# ChassisCab-mega328.net
KiCad netlist of a schematic drawn in EAGLE
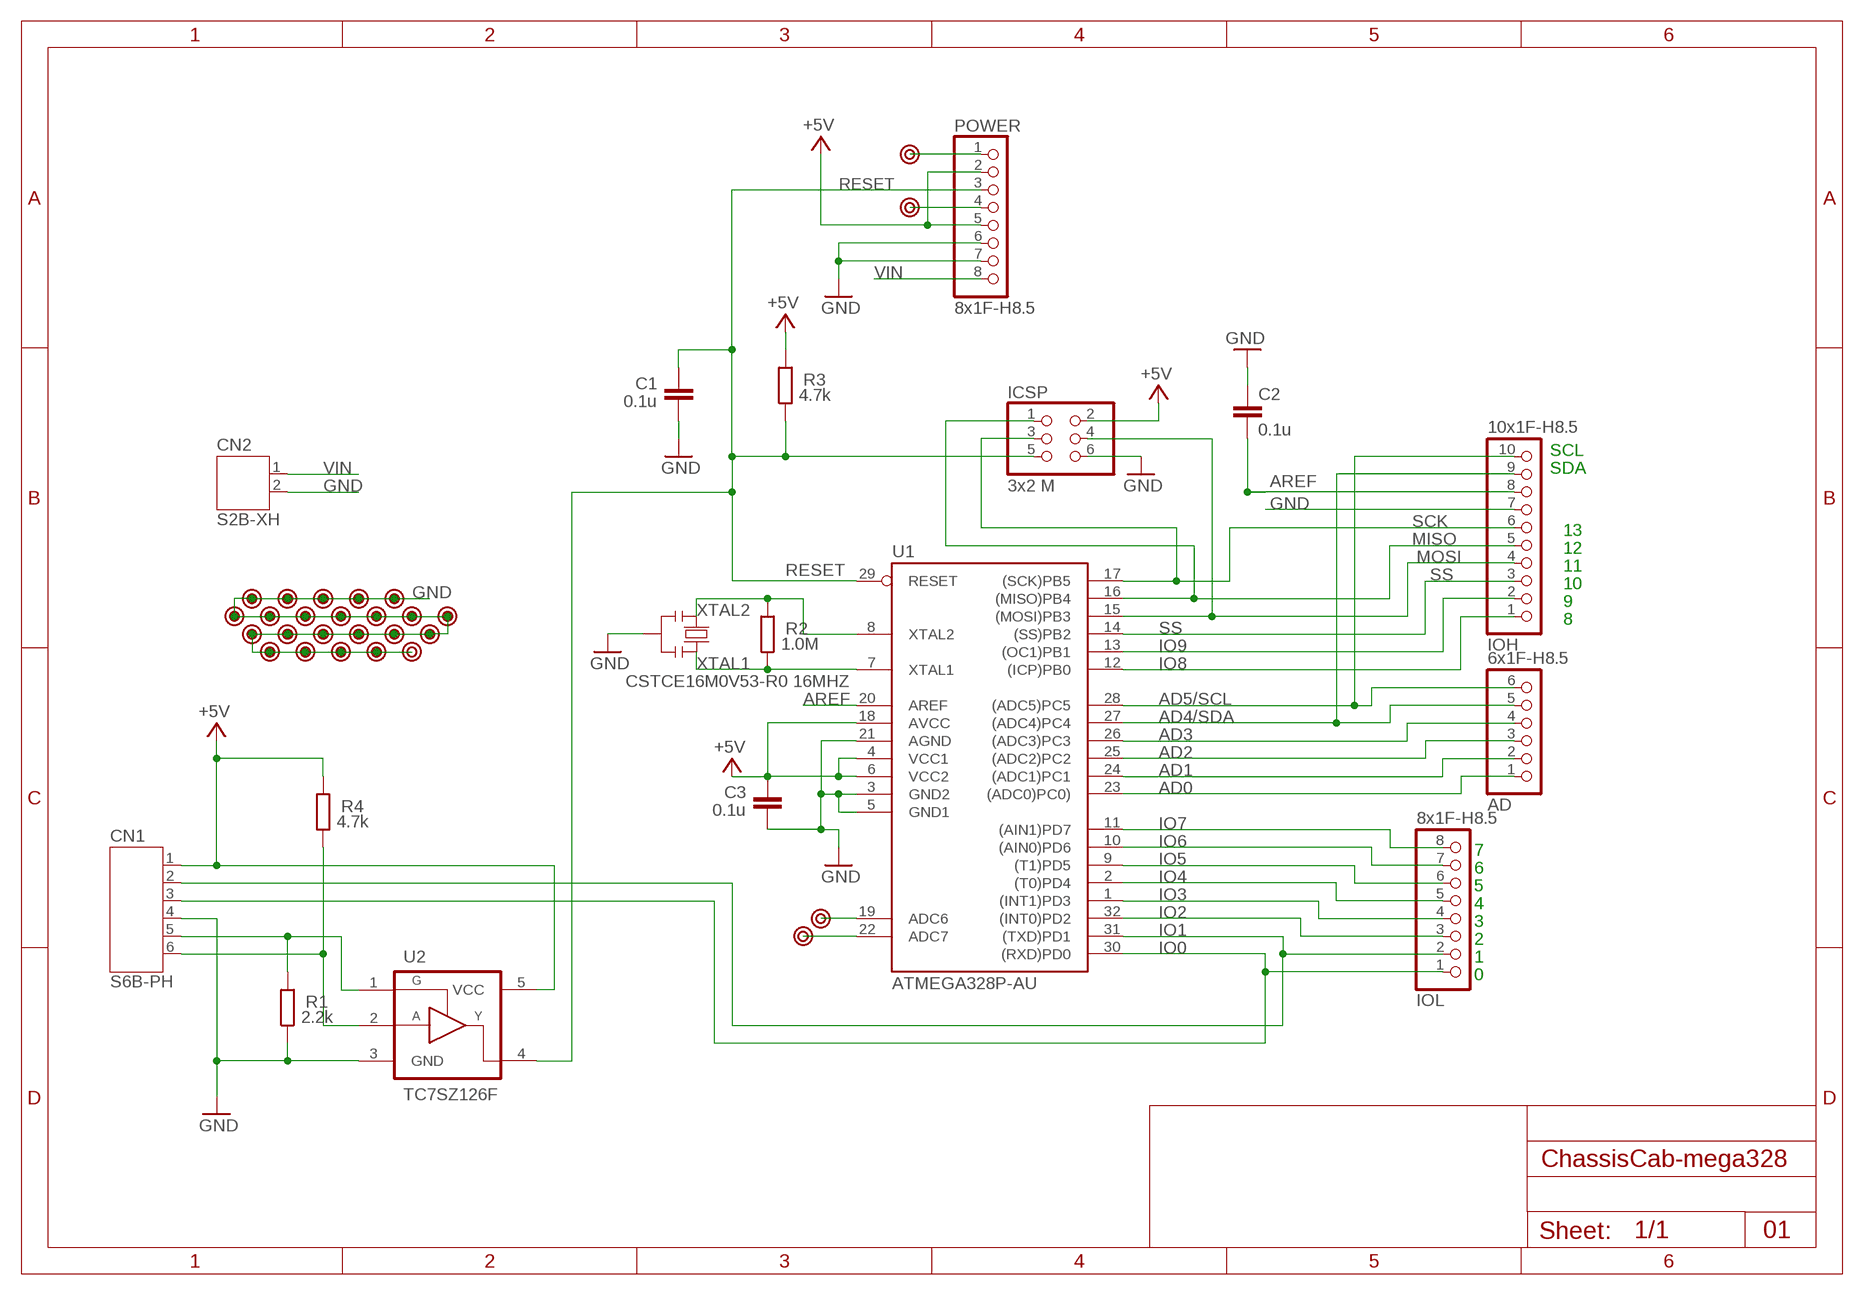
[diagram p0: schematic, sheet 1]

(export (version "E")
  (design (tool "Eeschema 10.0.6"))
  (components
    (comp (ref "AD")
      (value "6x1F-H8.5")
      (footprint "eagle-import:1X06")
      (libsource (lib "eagle-import") (part "PINHD-1X6"))
    )
    (comp (ref "C1")
      (value "0.1u")
      (footprint "eagle-import:C0603")
      (libsource (lib "eagle-import") (part "C-EUC0603"))
    )
    (comp (ref "C2")
      (value "0.1u")
      (footprint "eagle-import:C0603")
      (libsource (lib "eagle-import") (part "C-EUC0603"))
    )
    (comp (ref "C3")
      (value "0.1u")
      (footprint "eagle-import:C0603")
      (libsource (lib "eagle-import") (part "C-EUC0603"))
    )
    (comp (ref "CN1")
      (value "S6B-PH")
      (footprint "eagle-import:S6B-PH")
      (libsource (lib "eagle-import") (part "S6B-PH"))
    )
    (comp (ref "CN2")
      (value "S2B-XH")
      (footprint "eagle-import:S2B-XH")
      (libsource (lib "eagle-import") (part "S2B-XH"))
    )
    (comp (ref "ICSP")
      (value "3x2 M")
      (footprint "eagle-import:2X03")
      (libsource (lib "eagle-import") (part "PINHD-2X3"))
    )
    (comp (ref "IOH")
      (value "10x1F-H8.5")
      (footprint "eagle-import:1X10")
      (libsource (lib "eagle-import") (part "PINHD-1X10_ARD"))
    )
    (comp (ref "IOL")
      (value "8x1F-H8.5")
      (footprint "eagle-import:1X08")
      (libsource (lib "eagle-import") (part "PINHD-1X8"))
    )
    (comp (ref "POWER")
      (value "8x1F-H8.5")
      (footprint "eagle-import:1X08")
      (libsource (lib "eagle-import") (part "PINHD-1X8"))
    )
    (comp (ref "R1")
      (value "2.2k")
      (footprint "eagle-import:R0603")
      (libsource (lib "eagle-import") (part "R-EU_R0603"))
    )
    (comp (ref "R2")
      (value "1.0M")
      (footprint "eagle-import:R0603")
      (libsource (lib "eagle-import") (part "R-EU_R0603"))
    )
    (comp (ref "R3")
      (value "4.7k")
      (footprint "eagle-import:R0603")
      (libsource (lib "eagle-import") (part "R-EU_R0603"))
    )
    (comp (ref "R4")
      (value "4.7k")
      (footprint "eagle-import:R0603")
      (libsource (lib "eagle-import") (part "R-EU_R0603"))
    )
    (comp (ref "U$1")
      (value "PAD")
      (footprint "eagle-import:PAD")
      (libsource (lib "eagle-import") (part "PAD"))
    )
    (comp (ref "U$2")
      (value "PAD")
      (footprint "eagle-import:PAD")
      (libsource (lib "eagle-import") (part "PAD"))
    )
    (comp (ref "U$3")
      (value "PAD")
      (footprint "eagle-import:PAD")
      (libsource (lib "eagle-import") (part "PAD"))
    )
    (comp (ref "U$4")
      (value "PAD")
      (footprint "eagle-import:PAD")
      (libsource (lib "eagle-import") (part "PAD"))
    )
    (comp (ref "U$5")
      (value "PAD")
      (footprint "eagle-import:PAD")
      (libsource (lib "eagle-import") (part "PAD"))
    )
    (comp (ref "U$6")
      (value "PAD")
      (footprint "eagle-import:PAD")
      (libsource (lib "eagle-import") (part "PAD"))
    )
    (comp (ref "U$7")
      (value "PAD")
      (footprint "eagle-import:PAD")
      (libsource (lib "eagle-import") (part "PAD"))
    )
    (comp (ref "U$8")
      (value "PAD")
      (footprint "eagle-import:PAD")
      (libsource (lib "eagle-import") (part "PAD"))
    )
    (comp (ref "U$9")
      (value "PAD")
      (footprint "eagle-import:PAD")
      (libsource (lib "eagle-import") (part "PAD"))
    )
    (comp (ref "U$10")
      (value "PAD")
      (footprint "eagle-import:PAD")
      (libsource (lib "eagle-import") (part "PAD"))
    )
    (comp (ref "U$11")
      (value "PAD")
      (footprint "eagle-import:PAD")
      (libsource (lib "eagle-import") (part "PAD"))
    )
    (comp (ref "U$12")
      (value "PAD")
      (footprint "eagle-import:PAD")
      (libsource (lib "eagle-import") (part "PAD"))
    )
    (comp (ref "U$13")
      (value "PAD")
      (footprint "eagle-import:PAD")
      (libsource (lib "eagle-import") (part "PAD"))
    )
    (comp (ref "U$14")
      (value "PAD")
      (footprint "eagle-import:PAD")
      (libsource (lib "eagle-import") (part "PAD"))
    )
    (comp (ref "U$15")
      (value "PAD")
      (footprint "eagle-import:PAD")
      (libsource (lib "eagle-import") (part "PAD"))
    )
    (comp (ref "U$16")
      (value "PAD")
      (footprint "eagle-import:PAD")
      (libsource (lib "eagle-import") (part "PAD"))
    )
    (comp (ref "U$17")
      (value "PAD")
      (footprint "eagle-import:PAD")
      (libsource (lib "eagle-import") (part "PAD"))
    )
    (comp (ref "U$18")
      (value "PAD")
      (footprint "eagle-import:PAD")
      (libsource (lib "eagle-import") (part "PAD"))
    )
    (comp (ref "U$19")
      (value "PAD")
      (footprint "eagle-import:PAD")
      (libsource (lib "eagle-import") (part "PAD"))
    )
    (comp (ref "U$20")
      (value "PAD")
      (footprint "eagle-import:PAD")
      (libsource (lib "eagle-import") (part "PAD"))
    )
    (comp (ref "U$21")
      (value "PAD")
      (footprint "eagle-import:PAD")
      (libsource (lib "eagle-import") (part "PAD"))
    )
    (comp (ref "U$22")
      (value "PAD")
      (footprint "eagle-import:PAD")
      (libsource (lib "eagle-import") (part "PAD"))
    )
    (comp (ref "U$23")
      (value "PAD")
      (footprint "eagle-import:PAD")
      (libsource (lib "eagle-import") (part "PAD"))
    )
    (comp (ref "U$24")
      (value "PAD")
      (footprint "eagle-import:PAD")
      (libsource (lib "eagle-import") (part "PAD"))
    )
    (comp (ref "U$25")
      (value "PAD")
      (footprint "eagle-import:PAD")
      (libsource (lib "eagle-import") (part "PAD"))
    )
    (comp (ref "U$26")
      (value "PAD")
      (footprint "eagle-import:PAD")
      (libsource (lib "eagle-import") (part "PAD"))
    )
    (comp (ref "U$27")
      (value "PAD")
      (footprint "eagle-import:PAD")
      (libsource (lib "eagle-import") (part "PAD"))
    )
    (comp (ref "U1")
      (value "ATMEGA328P-AU")
      (footprint "eagle-import:TQFP32")
      (libsource (lib "eagle-import") (part "ATMEGA328P-AU"))
    )
    (comp (ref "U2")
      (value "TC7SZ126F")
      (footprint "eagle-import:SMV")
      (libsource (lib "eagle-import") (part "TC7SZ126F"))
    )
    (comp (ref "X1")
      (value "CSTCE16M0V53-R0 16MHZ")
      (footprint "eagle-import:CSTCE_V")
      (libsource (lib "eagle-import") (part "CSTCE16M0V53-R0"))
    )
  )
  (nets
    (net (code "1") (name "+5V") (class "Default")
      (node (ref "C3") (pin "2") (pinfunction "2_2") (pintype "passive"))
      (node (ref "CN1") (pin "1") (pinfunction "1_1") (pintype "passive"))
      (node (ref "ICSP") (pin "2") (pinfunction "2_2") (pintype "passive"))
      (node (ref "POWER") (pin "2") (pinfunction "2_2") (pintype "passive"))
      (node (ref "POWER") (pin "5") (pinfunction "5_5") (pintype "passive"))
      (node (ref "R3") (pin "2") (pinfunction "2_2") (pintype "passive"))
      (node (ref "R4") (pin "2") (pinfunction "2_2") (pintype "passive"))
      (node (ref "U1") (pin "18") (pinfunction "AVCC_18") (pintype "power_in"))
      (node (ref "U1") (pin "4") (pinfunction "VCC1_4") (pintype "power_in"))
      (node (ref "U1") (pin "6") (pinfunction "VCC2_6") (pintype "power_in"))
      (node (ref "U2") (pin "5") (pinfunction "VCC_5") (pintype "power_in"))
    )
    (net (code "2") (name "/AD0") (class "Default")
      (node (ref "AD") (pin "1") (pinfunction "1_1") (pintype "passive"))
      (node (ref "U1") (pin "23") (pinfunction "(ADC0)PC0)_23") (pintype "bidirectional"))
    )
    (net (code "3") (name "/AD1") (class "Default")
      (node (ref "AD") (pin "2") (pinfunction "2_2") (pintype "passive"))
      (node (ref "U1") (pin "24") (pinfunction "(ADC1)PC1_24") (pintype "bidirectional"))
    )
    (net (code "4") (name "/AD2") (class "Default")
      (node (ref "AD") (pin "3") (pinfunction "3_3") (pintype "passive"))
      (node (ref "U1") (pin "25") (pinfunction "(ADC2)PC2_25") (pintype "bidirectional"))
    )
    (net (code "5") (name "/AD3") (class "Default")
      (node (ref "AD") (pin "4") (pinfunction "4_4") (pintype "passive"))
      (node (ref "U1") (pin "26") (pinfunction "(ADC3)PC3_26") (pintype "bidirectional"))
    )
    (net (code "6") (name "/AD4{slash}SDA") (class "Default")
      (node (ref "AD") (pin "5") (pinfunction "5_5") (pintype "passive"))
      (node (ref "IOH") (pin "9") (pinfunction "9_9") (pintype "passive"))
      (node (ref "U1") (pin "27") (pinfunction "(ADC4)PC4_27") (pintype "bidirectional"))
    )
    (net (code "7") (name "/AD5{slash}SCL") (class "Default")
      (node (ref "AD") (pin "6") (pinfunction "6_6") (pintype "passive"))
      (node (ref "IOH") (pin "10") (pinfunction "10_10") (pintype "passive"))
      (node (ref "U1") (pin "28") (pinfunction "(ADC5)PC5_28") (pintype "bidirectional"))
    )
    (net (code "8") (name "/AREF") (class "Default")
      (node (ref "C2") (pin "2") (pinfunction "2_2") (pintype "passive"))
      (node (ref "IOH") (pin "8") (pinfunction "8_8") (pintype "passive"))
      (node (ref "U1") (pin "20") (pinfunction "AREF_20") (pintype "passive"))
    )
    (net (code "9") (name "/IO0") (class "Default")
      (node (ref "CN1") (pin "3") (pinfunction "3_3") (pintype "passive"))
      (node (ref "IOL") (pin "1") (pinfunction "1_1") (pintype "passive"))
      (node (ref "U1") (pin "30") (pinfunction "(RXD)PD0_30") (pintype "bidirectional"))
    )
    (net (code "10") (name "/IO1") (class "Default")
      (node (ref "CN1") (pin "2") (pinfunction "2_2") (pintype "passive"))
      (node (ref "IOL") (pin "2") (pinfunction "2_2") (pintype "passive"))
      (node (ref "U1") (pin "31") (pinfunction "(TXD)PD1_31") (pintype "bidirectional"))
    )
    (net (code "11") (name "/IO2") (class "Default")
      (node (ref "IOL") (pin "3") (pinfunction "3_3") (pintype "passive"))
      (node (ref "U1") (pin "32") (pinfunction "(INT0)PD2_32") (pintype "bidirectional"))
    )
    (net (code "12") (name "/IO3") (class "Default")
      (node (ref "IOL") (pin "4") (pinfunction "4_4") (pintype "passive"))
      (node (ref "U1") (pin "1") (pinfunction "(INT1)PD3_1") (pintype "bidirectional"))
    )
    (net (code "13") (name "/IO4") (class "Default")
      (node (ref "IOL") (pin "5") (pinfunction "5_5") (pintype "passive"))
      (node (ref "U1") (pin "2") (pinfunction "(T0)PD4_2") (pintype "bidirectional"))
    )
    (net (code "14") (name "/IO5") (class "Default")
      (node (ref "IOL") (pin "6") (pinfunction "6_6") (pintype "passive"))
      (node (ref "U1") (pin "9") (pinfunction "(T1)PD5_9") (pintype "bidirectional"))
    )
    (net (code "15") (name "/IO6") (class "Default")
      (node (ref "IOL") (pin "7") (pinfunction "7_7") (pintype "passive"))
      (node (ref "U1") (pin "10") (pinfunction "(AIN0)PD6_10") (pintype "bidirectional"))
    )
    (net (code "16") (name "/IO7") (class "Default")
      (node (ref "IOL") (pin "8") (pinfunction "8_8") (pintype "passive"))
      (node (ref "U1") (pin "11") (pinfunction "(AIN1)PD7_11") (pintype "bidirectional"))
    )
    (net (code "17") (name "/IO8") (class "Default")
      (node (ref "IOH") (pin "1") (pinfunction "1_1") (pintype "passive"))
      (node (ref "U1") (pin "12") (pinfunction "(ICP)PB0_12") (pintype "bidirectional"))
    )
    (net (code "18") (name "/IO9") (class "Default")
      (node (ref "IOH") (pin "2") (pinfunction "2_2") (pintype "passive"))
      (node (ref "U1") (pin "13") (pinfunction "(OC1)PB1_13") (pintype "bidirectional"))
    )
    (net (code "19") (name "/MISO") (class "Default")
      (node (ref "ICSP") (pin "1") (pinfunction "1_1") (pintype "passive"))
      (node (ref "IOH") (pin "5") (pinfunction "5_5") (pintype "passive"))
      (node (ref "U1") (pin "16") (pinfunction "(MISO)PB4_16") (pintype "bidirectional"))
    )
    (net (code "20") (name "/MOSI") (class "Default")
      (node (ref "ICSP") (pin "4") (pinfunction "4_4") (pintype "passive"))
      (node (ref "IOH") (pin "4") (pinfunction "4_4") (pintype "passive"))
      (node (ref "U1") (pin "15") (pinfunction "(MOSI)PB3_15") (pintype "bidirectional"))
    )
    (net (code "21") (name "/RESET") (class "Default")
      (node (ref "C1") (pin "2") (pinfunction "2_2") (pintype "passive"))
      (node (ref "ICSP") (pin "5") (pinfunction "5_5") (pintype "passive"))
      (node (ref "POWER") (pin "3") (pinfunction "3_3") (pintype "passive"))
      (node (ref "R3") (pin "1") (pinfunction "1_1") (pintype "passive"))
      (node (ref "U1") (pin "29") (pinfunction "RESET_29") (pintype "input"))
      (node (ref "U2") (pin "4") (pinfunction "Y_4") (pintype "output"))
    )
    (net (code "22") (name "/SCK") (class "Default")
      (node (ref "ICSP") (pin "3") (pinfunction "3_3") (pintype "passive"))
      (node (ref "IOH") (pin "6") (pinfunction "6_6") (pintype "passive"))
      (node (ref "U1") (pin "17") (pinfunction "(SCK)PB5_17") (pintype "bidirectional"))
    )
    (net (code "23") (name "/SS") (class "Default")
      (node (ref "IOH") (pin "3") (pinfunction "3_3") (pintype "passive"))
      (node (ref "U1") (pin "14") (pinfunction "(SS)PB2_14") (pintype "bidirectional"))
    )
    (net (code "24") (name "/VIN") (class "Default")
      (node (ref "CN2") (pin "1") (pinfunction "1_1") (pintype "passive"))
      (node (ref "POWER") (pin "8") (pinfunction "8_8") (pintype "passive"))
    )
    (net (code "25") (name "/XTAL1") (class "Default")
      (node (ref "R2") (pin "1") (pinfunction "1_1") (pintype "passive"))
      (node (ref "U1") (pin "7") (pinfunction "XTAL1_7") (pintype "bidirectional"))
      (node (ref "X1") (pin "3") (pinfunction "3_3") (pintype "passive"))
    )
    (net (code "26") (name "/XTAL2") (class "Default")
      (node (ref "R2") (pin "2") (pinfunction "2_2") (pintype "passive"))
      (node (ref "U1") (pin "8") (pinfunction "XTAL2_8") (pintype "bidirectional"))
      (node (ref "X1") (pin "1") (pinfunction "1_1") (pintype "passive"))
    )
    (net (code "27") (name "GND") (class "Default")
      (node (ref "C1") (pin "1") (pinfunction "1_1") (pintype "passive"))
      (node (ref "C2") (pin "1") (pinfunction "1_1") (pintype "passive"))
      (node (ref "C3") (pin "1") (pinfunction "1_1") (pintype "passive"))
      (node (ref "CN1") (pin "4") (pinfunction "4_4") (pintype "passive"))
      (node (ref "CN2") (pin "2") (pinfunction "2_2") (pintype "passive"))
      (node (ref "ICSP") (pin "6") (pinfunction "6_6") (pintype "passive"))
      (node (ref "IOH") (pin "7") (pinfunction "7_7") (pintype "passive"))
      (node (ref "POWER") (pin "6") (pinfunction "6_6") (pintype "passive"))
      (node (ref "POWER") (pin "7") (pinfunction "7_7") (pintype "passive"))
      (node (ref "R1") (pin "1") (pinfunction "1_1") (pintype "passive"))
      (node (ref "U$10") (pin "1") (pinfunction "1_1") (pintype "passive"))
      (node (ref "U$11") (pin "1") (pinfunction "1_1") (pintype "passive"))
      (node (ref "U$12") (pin "1") (pinfunction "1_1") (pintype "passive"))
      (node (ref "U$13") (pin "1") (pinfunction "1_1") (pintype "passive"))
      (node (ref "U$14") (pin "1") (pinfunction "1_1") (pintype "passive"))
      (node (ref "U$15") (pin "1") (pinfunction "1_1") (pintype "passive"))
      (node (ref "U$16") (pin "1") (pinfunction "1_1") (pintype "passive"))
      (node (ref "U$17") (pin "1") (pinfunction "1_1") (pintype "passive"))
      (node (ref "U$18") (pin "1") (pinfunction "1_1") (pintype "passive"))
      (node (ref "U$19") (pin "1") (pinfunction "1_1") (pintype "passive"))
      (node (ref "U$20") (pin "1") (pinfunction "1_1") (pintype "passive"))
      (node (ref "U$21") (pin "1") (pinfunction "1_1") (pintype "passive"))
      (node (ref "U$22") (pin "1") (pinfunction "1_1") (pintype "passive"))
      (node (ref "U$23") (pin "1") (pinfunction "1_1") (pintype "passive"))
      (node (ref "U$24") (pin "1") (pinfunction "1_1") (pintype "passive"))
      (node (ref "U$27") (pin "1") (pinfunction "1_1") (pintype "passive"))
      (node (ref "U$3") (pin "1") (pinfunction "1_1") (pintype "passive"))
      (node (ref "U$4") (pin "1") (pinfunction "1_1") (pintype "passive"))
      (node (ref "U$5") (pin "1") (pinfunction "1_1") (pintype "passive"))
      (node (ref "U$6") (pin "1") (pinfunction "1_1") (pintype "passive"))
      (node (ref "U$7") (pin "1") (pinfunction "1_1") (pintype "passive"))
      (node (ref "U$8") (pin "1") (pinfunction "1_1") (pintype "passive"))
      (node (ref "U$9") (pin "1") (pinfunction "1_1") (pintype "passive"))
      (node (ref "U1") (pin "21") (pinfunction "AGND_21") (pintype "power_in"))
      (node (ref "U1") (pin "3") (pinfunction "GND2_3") (pintype "power_in"))
      (node (ref "U1") (pin "5") (pinfunction "GND1_5") (pintype "power_in"))
      (node (ref "U2") (pin "3") (pinfunction "GND_3") (pintype "power_in"))
      (node (ref "X1") (pin "2") (pinfunction "2_2") (pintype "power_in"))
    )
    (net (code "28") (name "Net-(POWER-Pad1)") (class "Default")
      (node (ref "POWER") (pin "1") (pinfunction "1_1") (pintype "passive"))
      (node (ref "U$25") (pin "1") (pinfunction "1_1") (pintype "passive"))
    )
    (net (code "29") (name "Net-(POWER-Pad4)") (class "Default")
      (node (ref "POWER") (pin "4") (pinfunction "4_4") (pintype "passive"))
      (node (ref "U$26") (pin "1") (pinfunction "1_1") (pintype "passive"))
    )
    (net (code "30") (name "Net-(U1-ADC6)") (class "Default")
      (node (ref "U$1") (pin "1") (pinfunction "1_1") (pintype "passive"))
      (node (ref "U1") (pin "19") (pinfunction "ADC6_19") (pintype "input"))
    )
    (net (code "31") (name "Net-(U1-ADC7)") (class "Default")
      (node (ref "U$2") (pin "1") (pinfunction "1_1") (pintype "passive"))
      (node (ref "U1") (pin "22") (pinfunction "ADC7_22") (pintype "input"))
    )
    (net (code "32") (name "Net-(U2-A)") (class "Default")
      (node (ref "CN1") (pin "6") (pinfunction "6_6") (pintype "passive"))
      (node (ref "R4") (pin "1") (pinfunction "1_1") (pintype "passive"))
      (node (ref "U2") (pin "2") (pinfunction "A_2") (pintype "input"))
    )
    (net (code "33") (name "Net-(U2-G)") (class "Default")
      (node (ref "CN1") (pin "5") (pinfunction "5_5") (pintype "passive"))
      (node (ref "R1") (pin "2") (pinfunction "2_2") (pintype "passive"))
      (node (ref "U2") (pin "1") (pinfunction "G_1") (pintype "input"))
    )
  )
)
